# Dual_Motor_Driver.net
KiCad netlist of a schematic drawn in EAGLE
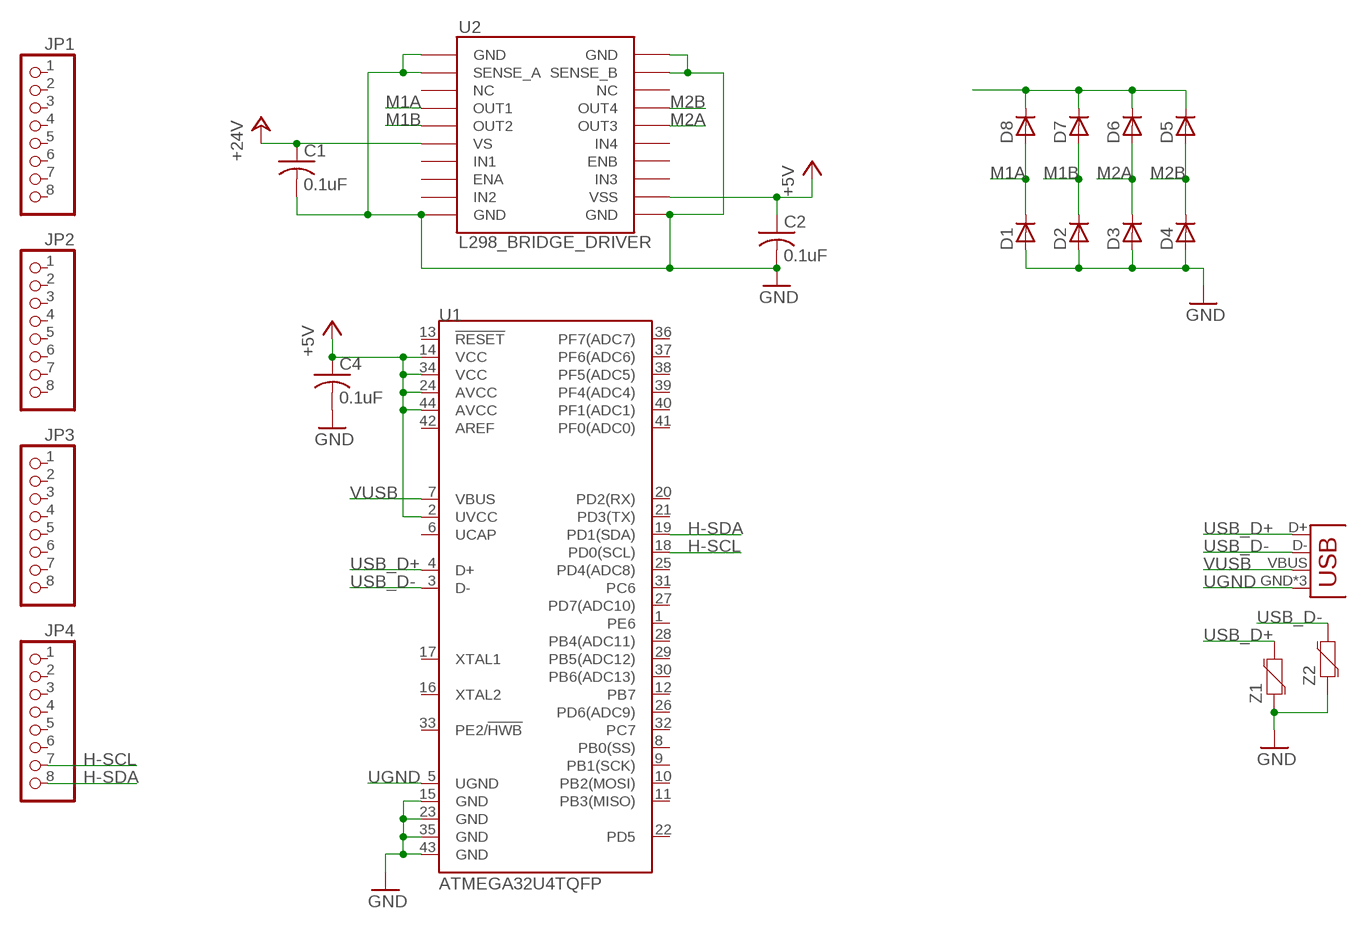
[diagram p0: schematic, sheet 1]

(export (version "E")
  (design (tool "Eeschema 10.0.6"))
  (components
    (comp (ref "C1")
      (value "0.1uF")
      (footprint "eagle-import:C0603")
      (libsource (lib "eagle-import") (part "C-USC0603"))
    )
    (comp (ref "C2")
      (value "0.1uF")
      (footprint "eagle-import:C0603")
      (libsource (lib "eagle-import") (part "C-USC0603"))
    )
    (comp (ref "C4")
      (value "0.1uF")
      (footprint "eagle-import:C0603")
      (libsource (lib "eagle-import") (part "C-USC0603"))
    )
    (comp (ref "D1")
      (value "D-SOD123")
      (footprint "eagle-import:SOD123")
      (fields (field (name "PART#") "CDBW140-G"))
      (libsource (lib "eagle-import") (part "D-SOD123"))
    )
    (comp (ref "D2")
      (value "D-SOD123")
      (footprint "eagle-import:SOD123")
      (fields (field (name "PART#") "CDBW140-G"))
      (libsource (lib "eagle-import") (part "D-SOD123"))
    )
    (comp (ref "D3")
      (value "D-SOD123")
      (footprint "eagle-import:SOD123")
      (fields (field (name "PART#") "CDBW140-G"))
      (libsource (lib "eagle-import") (part "D-SOD123"))
    )
    (comp (ref "D4")
      (value "D-SOD123")
      (footprint "eagle-import:SOD123")
      (fields (field (name "PART#") "CDBW140-G"))
      (libsource (lib "eagle-import") (part "D-SOD123"))
    )
    (comp (ref "D5")
      (value "D-SOD123")
      (footprint "eagle-import:SOD123")
      (fields (field (name "PART#") "CDBW140-G"))
      (libsource (lib "eagle-import") (part "D-SOD123"))
    )
    (comp (ref "D6")
      (value "D-SOD123")
      (footprint "eagle-import:SOD123")
      (fields (field (name "PART#") "CDBW140-G"))
      (libsource (lib "eagle-import") (part "D-SOD123"))
    )
    (comp (ref "D7")
      (value "D-SOD123")
      (footprint "eagle-import:SOD123")
      (fields (field (name "PART#") "CDBW140-G"))
      (libsource (lib "eagle-import") (part "D-SOD123"))
    )
    (comp (ref "D8")
      (value "D-SOD123")
      (footprint "eagle-import:SOD123")
      (fields (field (name "PART#") "CDBW140-G"))
      (libsource (lib "eagle-import") (part "D-SOD123"))
    )
    (comp (ref "JP1")
      (value "PINHD-1X81X08_NO_SILK")
      (footprint "eagle-import:1X08_NO_SS")
      (libsource (lib "eagle-import") (part "PINHD-1X81X08_NO_SILK"))
    )
    (comp (ref "JP2")
      (value "PINHD-1X81X08_NO_SILK")
      (footprint "eagle-import:1X08_NO_SS")
      (libsource (lib "eagle-import") (part "PINHD-1X81X08_NO_SILK"))
    )
    (comp (ref "JP3")
      (value "PINHD-1X81X08_NO_SILK")
      (footprint "eagle-import:1X08_NO_SS")
      (libsource (lib "eagle-import") (part "PINHD-1X81X08_NO_SILK"))
    )
    (comp (ref "JP4")
      (value "PINHD-1X81X08_NO_SILK")
      (footprint "eagle-import:1X08_NO_SS")
      (libsource (lib "eagle-import") (part "PINHD-1X81X08_NO_SILK"))
    )
    (comp (ref "JP5")
      (value "USB-MICROB")
      (footprint "eagle-import:USB-MICROB")
      (libsource (lib "eagle-import") (part "USB-MICROB"))
    )
    (comp (ref "U1")
      (value "ATMEGA32U4TQFP")
      (footprint "eagle-import:SPARKFUN-DIGITALIC_TQFP44")
      (libsource (lib "eagle-import") (part "ATMEGA32U4TQFP"))
    )
    (comp (ref "U2")
      (value "L298_BRIDGE_DRIVER")
      (footprint "eagle-import:POWERSO20")
      (libsource (lib "eagle-import") (part "L298_BRIDGE_DRIVER"))
    )
    (comp (ref "Z1")
      (value "VARISTOR-0603")
      (footprint "eagle-import:0603-RES")
      (fields (field (name "PART#") "CG0603MLC-05E"))
      (libsource (lib "eagle-import") (part "VARISTOR-0603"))
    )
    (comp (ref "Z2")
      (value "VARISTOR-0603")
      (footprint "eagle-import:0603-RES")
      (fields (field (name "PART#") "CG0603MLC-05E"))
      (libsource (lib "eagle-import") (part "VARISTOR-0603"))
    )
  )
  (nets
    (net (code "1") (name "+5V") (class "Default")
      (node (ref "C2") (pin "1") (pinfunction "1_1") (pintype "passive"))
      (node (ref "C4") (pin "1") (pinfunction "1_1") (pintype "passive"))
      (node (ref "U1") (pin "14") (pinfunction "VCC_14") (pintype "bidirectional"))
      (node (ref "U1") (pin "2") (pinfunction "UVCC_2") (pintype "bidirectional"))
      (node (ref "U1") (pin "24") (pinfunction "AVCC_24") (pintype "bidirectional"))
      (node (ref "U1") (pin "34") (pinfunction "VCC_34") (pintype "bidirectional"))
      (node (ref "U1") (pin "44") (pinfunction "AVCC_44") (pintype "bidirectional"))
      (node (ref "U2") (pin "12") (pinfunction "VSS_12") (pintype "bidirectional"))
    )
    (net (code "2") (name "+24V") (class "Default")
      (node (ref "C1") (pin "1") (pinfunction "1_1") (pintype "passive"))
      (node (ref "U2") (pin "6") (pinfunction "VS_6") (pintype "bidirectional"))
    )
    (net (code "3") (name "/H-SCL") (class "Default")
      (node (ref "JP4") (pin "7") (pinfunction "7_7") (pintype "passive"))
      (node (ref "U1") (pin "18") (pinfunction "PD0(SCL)_18") (pintype "bidirectional"))
    )
    (net (code "4") (name "/H-SDA") (class "Default")
      (node (ref "JP4") (pin "8") (pinfunction "8_8") (pintype "passive"))
      (node (ref "U1") (pin "19") (pinfunction "PD1(SDA)_19") (pintype "bidirectional"))
    )
    (net (code "5") (name "/M1A") (class "Default")
      (node (ref "D1") (pin "1") (pinfunction "C_1") (pintype "passive"))
      (node (ref "D8") (pin "2") (pinfunction "A_2") (pintype "passive"))
      (node (ref "U2") (pin "4") (pinfunction "OUT1_4") (pintype "bidirectional"))
    )
    (net (code "6") (name "/M1B") (class "Default")
      (node (ref "D2") (pin "1") (pinfunction "C_1") (pintype "passive"))
      (node (ref "D7") (pin "2") (pinfunction "A_2") (pintype "passive"))
      (node (ref "U2") (pin "5") (pinfunction "OUT2_5") (pintype "bidirectional"))
    )
    (net (code "7") (name "/M2A") (class "Default")
      (node (ref "D3") (pin "1") (pinfunction "C_1") (pintype "passive"))
      (node (ref "D6") (pin "2") (pinfunction "A_2") (pintype "passive"))
      (node (ref "U2") (pin "16") (pinfunction "OUT3_16") (pintype "bidirectional"))
    )
    (net (code "8") (name "/M2B") (class "Default")
      (node (ref "D4") (pin "1") (pinfunction "C_1") (pintype "passive"))
      (node (ref "D5") (pin "2") (pinfunction "A_2") (pintype "passive"))
      (node (ref "U2") (pin "17") (pinfunction "OUT4_17") (pintype "bidirectional"))
    )
    (net (code "9") (name "/UGND") (class "Default")
      (node (ref "JP5") (pin "GND") (pinfunction "GND_GND") (pintype "bidirectional"))
      (node (ref "JP5") (pin "MT1") (pinfunction "GND_MT1") (pintype "bidirectional"))
      (node (ref "JP5") (pin "MT2") (pinfunction "GND_MT2") (pintype "bidirectional"))
      (node (ref "U1") (pin "5") (pinfunction "UGND_5") (pintype "bidirectional"))
    )
    (net (code "10") (name "/USB_D+") (class "Default")
      (node (ref "JP5") (pin "D+") (pinfunction "D+_D+") (pintype "bidirectional"))
      (node (ref "U1") (pin "4") (pinfunction "D+_4") (pintype "bidirectional"))
      (node (ref "Z1") (pin "2") (pinfunction "2_2") (pintype "passive"))
    )
    (net (code "11") (name "/USB_D-") (class "Default")
      (node (ref "JP5") (pin "D-") (pinfunction "D-_D-") (pintype "bidirectional"))
      (node (ref "U1") (pin "3") (pinfunction "D-_3") (pintype "bidirectional"))
      (node (ref "Z2") (pin "2") (pinfunction "2_2") (pintype "passive"))
    )
    (net (code "12") (name "/VUSB") (class "Default")
      (node (ref "JP5") (pin "VBUS") (pinfunction "VBUS_VBUS") (pintype "bidirectional"))
      (node (ref "U1") (pin "7") (pinfunction "VBUS_7") (pintype "bidirectional"))
    )
    (net (code "13") (name "GND") (class "Default")
      (node (ref "C1") (pin "2") (pinfunction "2_2") (pintype "passive"))
      (node (ref "C2") (pin "2") (pinfunction "2_2") (pintype "passive"))
      (node (ref "C4") (pin "2") (pinfunction "2_2") (pintype "passive"))
      (node (ref "D1") (pin "2") (pinfunction "A_2") (pintype "passive"))
      (node (ref "D2") (pin "2") (pinfunction "A_2") (pintype "passive"))
      (node (ref "D3") (pin "2") (pinfunction "A_2") (pintype "passive"))
      (node (ref "D4") (pin "2") (pinfunction "A_2") (pintype "passive"))
      (node (ref "U1") (pin "15") (pinfunction "GND_15") (pintype "bidirectional"))
      (node (ref "U1") (pin "23") (pinfunction "GND_23") (pintype "bidirectional"))
      (node (ref "U1") (pin "35") (pinfunction "GND_35") (pintype "bidirectional"))
      (node (ref "U1") (pin "43") (pinfunction "GND_43") (pintype "bidirectional"))
      (node (ref "U2") (pin "1") (pinfunction "GND_1") (pintype "bidirectional"))
      (node (ref "U2") (pin "10") (pinfunction "GND_10") (pintype "bidirectional"))
      (node (ref "U2") (pin "11") (pinfunction "GND_11") (pintype "bidirectional"))
      (node (ref "U2") (pin "19") (pinfunction "SENSE_B_19") (pintype "bidirectional"))
      (node (ref "U2") (pin "2") (pinfunction "SENSE_A_2") (pintype "bidirectional"))
      (node (ref "U2") (pin "20") (pinfunction "GND_20") (pintype "bidirectional"))
      (node (ref "Z1") (pin "1") (pinfunction "1_1") (pintype "passive"))
      (node (ref "Z2") (pin "1") (pinfunction "1_1") (pintype "passive"))
    )
    (net (code "14") (name "Net-(D5-C)") (class "Default")
      (node (ref "D5") (pin "1") (pinfunction "C_1") (pintype "passive"))
      (node (ref "D6") (pin "1") (pinfunction "C_1") (pintype "passive"))
      (node (ref "D7") (pin "1") (pinfunction "C_1") (pintype "passive"))
      (node (ref "D8") (pin "1") (pinfunction "C_1") (pintype "passive"))
    )
    (net (code "15") (name "unconnected-(JP1-Pad1)") (class "Default")
      (node (ref "JP1") (pin "1") (pinfunction "1_1") (pintype "passive"))
    )
    (net (code "16") (name "unconnected-(JP1-Pad2)") (class "Default")
      (node (ref "JP1") (pin "2") (pinfunction "2_2") (pintype "passive"))
    )
    (net (code "17") (name "unconnected-(JP1-Pad3)") (class "Default")
      (node (ref "JP1") (pin "3") (pinfunction "3_3") (pintype "passive"))
    )
    (net (code "18") (name "unconnected-(JP1-Pad4)") (class "Default")
      (node (ref "JP1") (pin "4") (pinfunction "4_4") (pintype "passive"))
    )
    (net (code "19") (name "unconnected-(JP1-Pad5)") (class "Default")
      (node (ref "JP1") (pin "5") (pinfunction "5_5") (pintype "passive"))
    )
    (net (code "20") (name "unconnected-(JP1-Pad6)") (class "Default")
      (node (ref "JP1") (pin "6") (pinfunction "6_6") (pintype "passive"))
    )
    (net (code "21") (name "unconnected-(JP1-Pad7)") (class "Default")
      (node (ref "JP1") (pin "7") (pinfunction "7_7") (pintype "passive"))
    )
    (net (code "22") (name "unconnected-(JP1-Pad8)") (class "Default")
      (node (ref "JP1") (pin "8") (pinfunction "8_8") (pintype "passive"))
    )
    (net (code "23") (name "unconnected-(JP2-Pad1)") (class "Default")
      (node (ref "JP2") (pin "1") (pinfunction "1_1") (pintype "passive"))
    )
    (net (code "24") (name "unconnected-(JP2-Pad2)") (class "Default")
      (node (ref "JP2") (pin "2") (pinfunction "2_2") (pintype "passive"))
    )
    (net (code "25") (name "unconnected-(JP2-Pad3)") (class "Default")
      (node (ref "JP2") (pin "3") (pinfunction "3_3") (pintype "passive"))
    )
    (net (code "26") (name "unconnected-(JP2-Pad4)") (class "Default")
      (node (ref "JP2") (pin "4") (pinfunction "4_4") (pintype "passive"))
    )
    (net (code "27") (name "unconnected-(JP2-Pad5)") (class "Default")
      (node (ref "JP2") (pin "5") (pinfunction "5_5") (pintype "passive"))
    )
    (net (code "28") (name "unconnected-(JP2-Pad6)") (class "Default")
      (node (ref "JP2") (pin "6") (pinfunction "6_6") (pintype "passive"))
    )
    (net (code "29") (name "unconnected-(JP2-Pad7)") (class "Default")
      (node (ref "JP2") (pin "7") (pinfunction "7_7") (pintype "passive"))
    )
    (net (code "30") (name "unconnected-(JP2-Pad8)") (class "Default")
      (node (ref "JP2") (pin "8") (pinfunction "8_8") (pintype "passive"))
    )
    (net (code "31") (name "unconnected-(JP3-Pad1)") (class "Default")
      (node (ref "JP3") (pin "1") (pinfunction "1_1") (pintype "passive"))
    )
    (net (code "32") (name "unconnected-(JP3-Pad2)") (class "Default")
      (node (ref "JP3") (pin "2") (pinfunction "2_2") (pintype "passive"))
    )
    (net (code "33") (name "unconnected-(JP3-Pad3)") (class "Default")
      (node (ref "JP3") (pin "3") (pinfunction "3_3") (pintype "passive"))
    )
    (net (code "34") (name "unconnected-(JP3-Pad4)") (class "Default")
      (node (ref "JP3") (pin "4") (pinfunction "4_4") (pintype "passive"))
    )
    (net (code "35") (name "unconnected-(JP3-Pad5)") (class "Default")
      (node (ref "JP3") (pin "5") (pinfunction "5_5") (pintype "passive"))
    )
    (net (code "36") (name "unconnected-(JP3-Pad6)") (class "Default")
      (node (ref "JP3") (pin "6") (pinfunction "6_6") (pintype "passive"))
    )
    (net (code "37") (name "unconnected-(JP3-Pad7)") (class "Default")
      (node (ref "JP3") (pin "7") (pinfunction "7_7") (pintype "passive"))
    )
    (net (code "38") (name "unconnected-(JP3-Pad8)") (class "Default")
      (node (ref "JP3") (pin "8") (pinfunction "8_8") (pintype "passive"))
    )
    (net (code "39") (name "unconnected-(JP4-Pad1)") (class "Default")
      (node (ref "JP4") (pin "1") (pinfunction "1_1") (pintype "passive"))
    )
    (net (code "40") (name "unconnected-(JP4-Pad2)") (class "Default")
      (node (ref "JP4") (pin "2") (pinfunction "2_2") (pintype "passive"))
    )
    (net (code "41") (name "unconnected-(JP4-Pad3)") (class "Default")
      (node (ref "JP4") (pin "3") (pinfunction "3_3") (pintype "passive"))
    )
    (net (code "42") (name "unconnected-(JP4-Pad4)") (class "Default")
      (node (ref "JP4") (pin "4") (pinfunction "4_4") (pintype "passive"))
    )
    (net (code "43") (name "unconnected-(JP4-Pad5)") (class "Default")
      (node (ref "JP4") (pin "5") (pinfunction "5_5") (pintype "passive"))
    )
    (net (code "44") (name "unconnected-(JP4-Pad6)") (class "Default")
      (node (ref "JP4") (pin "6") (pinfunction "6_6") (pintype "passive"))
    )
    (net (code "45") (name "unconnected-(U1-AREF-Pad42)") (class "Default")
      (node (ref "U1") (pin "42") (pinfunction "AREF_42") (pintype "bidirectional"))
    )
    (net (code "46") (name "unconnected-(U1-PB0(SS)-Pad8)") (class "Default")
      (node (ref "U1") (pin "8") (pinfunction "PB0(SS)_8") (pintype "bidirectional"))
    )
    (net (code "47") (name "unconnected-(U1-PB1(SCK)-Pad9)") (class "Default")
      (node (ref "U1") (pin "9") (pinfunction "PB1(SCK)_9") (pintype "bidirectional"))
    )
    (net (code "48") (name "unconnected-(U1-PB2(MOSI)-Pad10)") (class "Default")
      (node (ref "U1") (pin "10") (pinfunction "PB2(MOSI)_10") (pintype "bidirectional"))
    )
    (net (code "49") (name "unconnected-(U1-PB3(MISO)-Pad11)") (class "Default")
      (node (ref "U1") (pin "11") (pinfunction "PB3(MISO)_11") (pintype "bidirectional"))
    )
    (net (code "50") (name "unconnected-(U1-PB4(ADC11)-Pad28)") (class "Default")
      (node (ref "U1") (pin "28") (pinfunction "PB4(ADC11)_28") (pintype "bidirectional"))
    )
    (net (code "51") (name "unconnected-(U1-PB5(ADC12)-Pad29)") (class "Default")
      (node (ref "U1") (pin "29") (pinfunction "PB5(ADC12)_29") (pintype "bidirectional"))
    )
    (net (code "52") (name "unconnected-(U1-PB6(ADC13)-Pad30)") (class "Default")
      (node (ref "U1") (pin "30") (pinfunction "PB6(ADC13)_30") (pintype "bidirectional"))
    )
    (net (code "53") (name "unconnected-(U1-PB7-Pad12)") (class "Default")
      (node (ref "U1") (pin "12") (pinfunction "PB7_12") (pintype "bidirectional"))
    )
    (net (code "54") (name "unconnected-(U1-PC6-Pad31)") (class "Default")
      (node (ref "U1") (pin "31") (pinfunction "PC6_31") (pintype "bidirectional"))
    )
    (net (code "55") (name "unconnected-(U1-PC7-Pad32)") (class "Default")
      (node (ref "U1") (pin "32") (pinfunction "PC7_32") (pintype "bidirectional"))
    )
    (net (code "56") (name "unconnected-(U1-PD2(RX)-Pad20)") (class "Default")
      (node (ref "U1") (pin "20") (pinfunction "PD2(RX)_20") (pintype "bidirectional"))
    )
    (net (code "57") (name "unconnected-(U1-PD3(TX)-Pad21)") (class "Default")
      (node (ref "U1") (pin "21") (pinfunction "PD3(TX)_21") (pintype "bidirectional"))
    )
    (net (code "58") (name "unconnected-(U1-PD4(ADC8)-Pad25)") (class "Default")
      (node (ref "U1") (pin "25") (pinfunction "PD4(ADC8)_25") (pintype "bidirectional"))
    )
    (net (code "59") (name "unconnected-(U1-PD5-Pad22)") (class "Default")
      (node (ref "U1") (pin "22") (pinfunction "PD5_22") (pintype "bidirectional"))
    )
    (net (code "60") (name "unconnected-(U1-PD6(ADC9)-Pad26)") (class "Default")
      (node (ref "U1") (pin "26") (pinfunction "PD6(ADC9)_26") (pintype "bidirectional"))
    )
    (net (code "61") (name "unconnected-(U1-PD7(ADC10)-Pad27)") (class "Default")
      (node (ref "U1") (pin "27") (pinfunction "PD7(ADC10)_27") (pintype "bidirectional"))
    )
    (net (code "62") (name "unconnected-(U1-PE2{slash}~{HWB}-Pad33)") (class "Default")
      (node (ref "U1") (pin "33") (pinfunction "PE2/~{HWB}_33") (pintype "bidirectional"))
    )
    (net (code "63") (name "unconnected-(U1-PE6-Pad1)") (class "Default")
      (node (ref "U1") (pin "1") (pinfunction "PE6_1") (pintype "bidirectional"))
    )
    (net (code "64") (name "unconnected-(U1-PF0(ADC0)-Pad41)") (class "Default")
      (node (ref "U1") (pin "41") (pinfunction "PF0(ADC0)_41") (pintype "bidirectional"))
    )
    (net (code "65") (name "unconnected-(U1-PF1(ADC1)-Pad40)") (class "Default")
      (node (ref "U1") (pin "40") (pinfunction "PF1(ADC1)_40") (pintype "bidirectional"))
    )
    (net (code "66") (name "unconnected-(U1-PF4(ADC4)-Pad39)") (class "Default")
      (node (ref "U1") (pin "39") (pinfunction "PF4(ADC4)_39") (pintype "bidirectional"))
    )
    (net (code "67") (name "unconnected-(U1-PF5(ADC5)-Pad38)") (class "Default")
      (node (ref "U1") (pin "38") (pinfunction "PF5(ADC5)_38") (pintype "bidirectional"))
    )
    (net (code "68") (name "unconnected-(U1-PF6(ADC6)-Pad37)") (class "Default")
      (node (ref "U1") (pin "37") (pinfunction "PF6(ADC6)_37") (pintype "bidirectional"))
    )
    (net (code "69") (name "unconnected-(U1-PF7(ADC7)-Pad36)") (class "Default")
      (node (ref "U1") (pin "36") (pinfunction "PF7(ADC7)_36") (pintype "bidirectional"))
    )
    (net (code "70") (name "unconnected-(U1-UCAP-Pad6)") (class "Default")
      (node (ref "U1") (pin "6") (pinfunction "UCAP_6") (pintype "bidirectional"))
    )
    (net (code "71") (name "unconnected-(U1-XTAL1-Pad17)") (class "Default")
      (node (ref "U1") (pin "17") (pinfunction "XTAL1_17") (pintype "bidirectional"))
    )
    (net (code "72") (name "unconnected-(U1-XTAL2-Pad16)") (class "Default")
      (node (ref "U1") (pin "16") (pinfunction "XTAL2_16") (pintype "bidirectional"))
    )
    (net (code "73") (name "unconnected-(U1-~{RESET}-Pad13)") (class "Default")
      (node (ref "U1") (pin "13") (pinfunction "~{RESET}_13") (pintype "bidirectional"))
    )
    (net (code "74") (name "unconnected-(U2-ENA-Pad8)") (class "Default")
      (node (ref "U2") (pin "8") (pinfunction "ENA_8") (pintype "bidirectional"))
    )
    (net (code "75") (name "unconnected-(U2-ENB-Pad14)") (class "Default")
      (node (ref "U2") (pin "14") (pinfunction "ENB_14") (pintype "bidirectional"))
    )
    (net (code "76") (name "unconnected-(U2-IN1-Pad7)") (class "Default")
      (node (ref "U2") (pin "7") (pinfunction "IN1_7") (pintype "bidirectional"))
    )
    (net (code "77") (name "unconnected-(U2-IN2-Pad9)") (class "Default")
      (node (ref "U2") (pin "9") (pinfunction "IN2_9") (pintype "bidirectional"))
    )
    (net (code "78") (name "unconnected-(U2-IN3-Pad13)") (class "Default")
      (node (ref "U2") (pin "13") (pinfunction "IN3_13") (pintype "bidirectional"))
    )
    (net (code "79") (name "unconnected-(U2-IN4-Pad15)") (class "Default")
      (node (ref "U2") (pin "15") (pinfunction "IN4_15") (pintype "bidirectional"))
    )
    (net (code "80") (name "unconnected-(U2-NC-Pad3)") (class "Default")
      (node (ref "U2") (pin "3") (pinfunction "NC_3") (pintype "bidirectional"))
    )
    (net (code "81") (name "unconnected-(U2-NC-Pad18)") (class "Default")
      (node (ref "U2") (pin "18") (pinfunction "NC_18") (pintype "bidirectional"))
    )
  )
)
